# Sheet1.net
KiCad netlist of a schematic drawn in Altium Designer
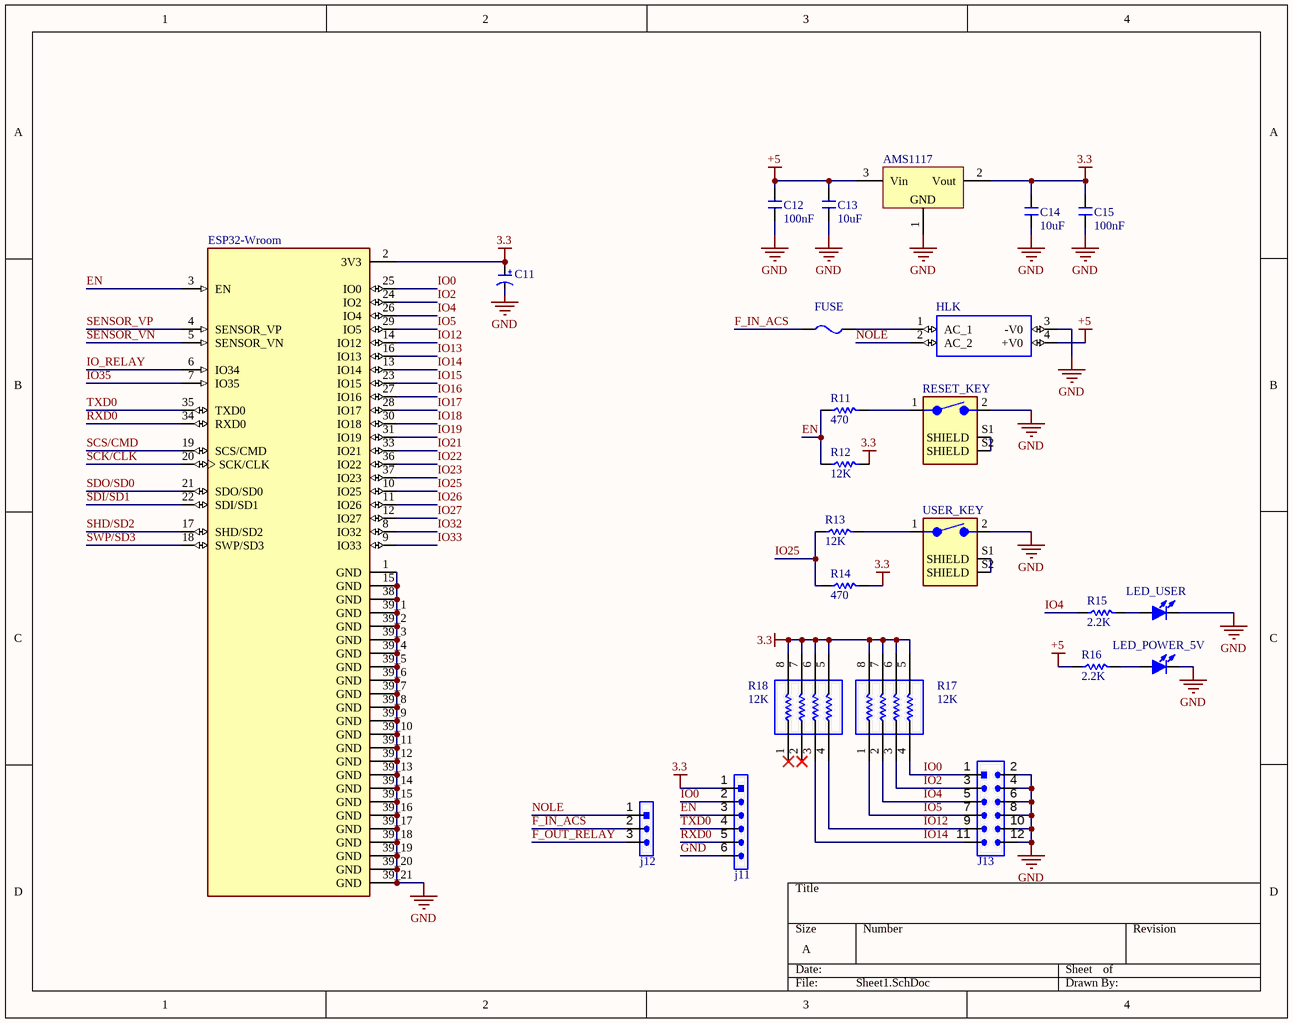
[diagram p0: Sheet1.SchDoc]

(export (version "E")
  (design (tool "Eeschema 10.0.6"))
  (components
    (comp (ref "AMS1117")
      (value "AMS1117-3V3")
      (footprint "SOT223_L")
      (description "Three-terminal regulator chip")
      (fields (field (name "版权归属") "源创客"))
      (libsource (lib "AltiumDesigner PCB Library") (part "AMS1117"))
    )
    (comp (ref "C11")
      (value "~")
      (footprint "CD A(3216)")
      (description "Solid Tantalum Chip Capacitor, Standard T491 Series - Industrial Grade")
      (fields (field (name "PUBLISHER") "Altium Limited"))
      (libsource (lib "AltiumDesigner PCB Library") (part "C-CD"))
    )
    (comp (ref "C12")
      (value "100nF")
      (footprint "C 0805")
      (description "Non-polar patch capacitor")
      (fields (field (name "版权归属") "源创客"))
      (libsource (lib "AltiumDesigner PCB Library") (part "C"))
    )
    (comp (ref "C13")
      (value "10uF")
      (footprint "C 0805")
      (description "Non-polar patch capacitor")
      (fields (field (name "版权归属") "源创客"))
      (libsource (lib "AltiumDesigner PCB Library") (part "C"))
    )
    (comp (ref "C14")
      (value "10uF")
      (footprint "C 0805")
      (description "Non-polar patch capacitor")
      (fields (field (name "版权归属") "源创客"))
      (libsource (lib "AltiumDesigner PCB Library") (part "C"))
    )
    (comp (ref "C15")
      (value "100nF")
      (footprint "C 0805")
      (description "Non-polar patch capacitor")
      (fields (field (name "版权归属") "源创客"))
      (libsource (lib "AltiumDesigner PCB Library") (part "C"))
    )
    (comp (ref "ESP32-Wroom")
      (value "ESP32-WROOM-32")
      (footprint "MODULE_ESP32-WROOM-32")
      (description "Bluetooth, WiFi Transceiver Module 2.4GHz ~ 2.5GHz Surface Mount")
      (fields (field (name "MF") "Espressif Systems") (field (name "DIGI-KEY_PART_NUMBER") "1904-1010-1-ND"))
      (libsource (lib "ESP32-WROOM-32") (part "ESP32-WROOM-32"))
    )
    (comp (ref "FUSE")
      (value "MSMD200-8V 2A")
      (footprint "FU 0805")
      (description "Chip fuse")
      (fields (field (name "版权归属") "源创客"))
      (libsource (lib "AltiumDesigner PCB Library") (part "FU"))
    )
    (comp (ref "HLK")
      (value "HLK-PM01")
      (footprint "HLKPM01")
      (fields (field (name "MF") "Hi-link") (field (name "MP") "hlk-pm01"))
      (libsource (lib "HLK-PM01") (part "HLK-PM01"))
    )
    (comp (ref "j11")
      (value "HDR-1X6")
      (footprint "HDR-1X6")
      (description "6P Connector")
      (fields (field (name "版权归属") "源创客"))
      (libsource (lib "AltiumDesigner PCB Library") (part "Header 6"))
    )
    (comp (ref "j12")
      (value "HDR-1X3")
      (footprint "HDR-1X3")
      (description "3P Connector")
      (fields (field (name "版权归属") "源创客"))
      (libsource (lib "AltiumDesigner PCB Library") (part "Header 3"))
    )
    (comp (ref "J13")
      (value "Header 6X2")
      (footprint "HDR-6X2")
      (description "6*2P Connector")
      (fields (field (name "版权归属") "源创客"))
      (libsource (lib "AltiumDesigner PCB Library") (part "Header  6X2"))
    )
    (comp (ref "LED_POWER_5V")
      (value "LED-SMD")
      (footprint "LED 0805R")
      (description "Patch LED")
      (fields (field (name "版权归属") "源创客"))
      (libsource (lib "AltiumDesigner PCB Library") (part "LED-SMD"))
    )
    (comp (ref "LED_USER")
      (value "LED-SMD")
      (footprint "LED 0805G")
      (description "Patch LED")
      (fields (field (name "版权归属") "源创客"))
      (libsource (lib "AltiumDesigner PCB Library") (part "LED-SMD"))
    )
    (comp (ref "R11")
      (value "470")
      (footprint "R 0805")
      (description "Chip resistor")
      (fields (field (name "版权归属") "源创客"))
      (libsource (lib "AltiumDesigner PCB Library") (part "R"))
    )
    (comp (ref "R12")
      (value "12K")
      (footprint "R 0805")
      (description "Chip resistor")
      (fields (field (name "版权归属") "源创客"))
      (libsource (lib "AltiumDesigner PCB Library") (part "R"))
    )
    (comp (ref "R13")
      (value "12K")
      (footprint "R 0805")
      (description "Chip resistor")
      (fields (field (name "版权归属") "源创客"))
      (libsource (lib "AltiumDesigner PCB Library") (part "R"))
    )
    (comp (ref "R14")
      (value "470")
      (footprint "R 0805")
      (description "Chip resistor")
      (fields (field (name "版权归属") "源创客"))
      (libsource (lib "AltiumDesigner PCB Library") (part "R"))
    )
    (comp (ref "R15")
      (value "2.2K")
      (footprint "R 0805")
      (description "Chip resistor")
      (fields (field (name "版权归属") "源创客"))
      (libsource (lib "AltiumDesigner PCB Library") (part "R"))
    )
    (comp (ref "R16")
      (value "2.2K")
      (footprint "R 0805")
      (description "Chip resistor")
      (fields (field (name "版权归属") "源创客"))
      (libsource (lib "AltiumDesigner PCB Library") (part "R"))
    )
    (comp (ref "R17")
      (value "12K")
      (footprint "RA0805 (4D02)-L")
      (description "4 way Chip Resistor Array")
      (libsource (lib "AltiumDesigner PCB Library") (part "R-ARR"))
    )
    (comp (ref "R18")
      (value "12K")
      (footprint "RA0805 (4D02)-L")
      (description "4 way Chip Resistor Array")
      (libsource (lib "AltiumDesigner PCB Library") (part "R-ARR"))
    )
    (comp (ref "RESET_KEY")
      (value "1-1825027-1")
      (footprint "SW_1-1825027-1")
      (description "Switch Push Button OFF _ON_ SPST Round Button 0.05A 24VDC Momentary Contact PC Pins Thru-Hole")
      (fields (field (name "MF") "TE Connectivity"))
      (libsource (lib "1-1825027-1") (part "1-1825027-1"))
    )
    (comp (ref "USER_KEY")
      (value "1-1825027-1")
      (footprint "SW_1-1825027-1")
      (description "Switch Push Button OFF _ON_ SPST Round Button 0.05A 24VDC Momentary Contact PC Pins Thru-Hole")
      (fields (field (name "MF") "TE Connectivity"))
      (libsource (lib "1-1825027-1") (part "1-1825027-1"))
    )
  )
  (nets
    (net (code "1") (name "+5") (class "Default")
      (node (ref "AMS1117") (pin "3") (pinfunction "Vin_3") (pintype "passive"))
      (node (ref "C12") (pin "2") (pinfunction "2_2") (pintype "passive"))
      (node (ref "C13") (pin "2") (pinfunction "2_2") (pintype "passive"))
      (node (ref "HLK") (pin "4") (pinfunction "+V0_4") (pintype "bidirectional"))
      (node (ref "R16") (pin "1") (pinfunction "1_1") (pintype "passive"))
    )
    (net (code "2") (name "/EN") (class "Default")
      (node (ref "ESP32-Wroom") (pin "3") (pinfunction "EN_3") (pintype "input"))
      (node (ref "R11") (pin "1") (pinfunction "1_1") (pintype "passive"))
      (node (ref "R12") (pin "1") (pinfunction "1_1") (pintype "passive"))
      (node (ref "j11") (pin "3") (pintype "passive"))
    )
    (net (code "3") (name "/F_IN_ACS") (class "Default")
      (node (ref "FUSE") (pin "1") (pinfunction "1_1") (pintype "passive"))
      (node (ref "j12") (pin "2") (pintype "passive"))
    )
    (net (code "4") (name "/F_OUT_RELAY") (class "Default") (node (ref "j12") (pin "3") (pintype "passive")))
    (net (code "5") (name "/IO0") (class "Default")
      (node (ref "ESP32-Wroom") (pin "25") (pinfunction "IO0_25") (pintype "bidirectional"))
      (node (ref "J13") (pin "1") (pintype "passive"))
      (node (ref "R17") (pin "4") (pinfunction "4_4") (pintype "passive"))
      (node (ref "j11") (pin "2") (pintype "passive"))
    )
    (net (code "6") (name "/IO2") (class "Default")
      (node (ref "ESP32-Wroom") (pin "24") (pinfunction "IO2_24") (pintype "bidirectional"))
      (node (ref "J13") (pin "3") (pintype "passive"))
      (node (ref "R17") (pin "3") (pinfunction "3_3") (pintype "passive"))
    )
    (net (code "7") (name "/IO4") (class "Default")
      (node (ref "ESP32-Wroom") (pin "26") (pinfunction "IO4_26") (pintype "bidirectional"))
      (node (ref "J13") (pin "5") (pintype "passive"))
      (node (ref "R15") (pin "1") (pinfunction "1_1") (pintype "passive"))
      (node (ref "R17") (pin "2") (pinfunction "2_2") (pintype "passive"))
    )
    (net (code "8") (name "/IO5") (class "Default")
      (node (ref "ESP32-Wroom") (pin "29") (pinfunction "IO5_29") (pintype "bidirectional"))
      (node (ref "J13") (pin "7") (pintype "passive"))
      (node (ref "R17") (pin "1") (pinfunction "1_1") (pintype "passive"))
    )
    (net (code "9") (name "/IO12") (class "Default")
      (node (ref "ESP32-Wroom") (pin "14") (pinfunction "IO12_14") (pintype "bidirectional"))
      (node (ref "J13") (pin "9") (pintype "passive"))
      (node (ref "R18") (pin "4") (pinfunction "4_4") (pintype "passive"))
    )
    (net (code "10") (name "/IO13") (class "Default")
      (node (ref "ESP32-Wroom") (pin "16") (pinfunction "IO13_16") (pintype "bidirectional"))
    )
    (net (code "11") (name "/IO14") (class "Default")
      (node (ref "ESP32-Wroom") (pin "13") (pinfunction "IO14_13") (pintype "bidirectional"))
      (node (ref "J13") (pin "11") (pintype "passive"))
      (node (ref "R18") (pin "3") (pinfunction "3_3") (pintype "passive"))
    )
    (net (code "12") (name "/IO15") (class "Default")
      (node (ref "ESP32-Wroom") (pin "23") (pinfunction "IO15_23") (pintype "bidirectional"))
    )
    (net (code "13") (name "/IO16") (class "Default")
      (node (ref "ESP32-Wroom") (pin "27") (pinfunction "IO16_27") (pintype "bidirectional"))
    )
    (net (code "14") (name "/IO17") (class "Default")
      (node (ref "ESP32-Wroom") (pin "28") (pinfunction "IO17_28") (pintype "bidirectional"))
    )
    (net (code "15") (name "/IO18") (class "Default")
      (node (ref "ESP32-Wroom") (pin "30") (pinfunction "IO18_30") (pintype "bidirectional"))
    )
    (net (code "16") (name "/IO19") (class "Default")
      (node (ref "ESP32-Wroom") (pin "31") (pinfunction "IO19_31") (pintype "bidirectional"))
    )
    (net (code "17") (name "/IO21") (class "Default")
      (node (ref "ESP32-Wroom") (pin "33") (pinfunction "IO21_33") (pintype "bidirectional"))
    )
    (net (code "18") (name "/IO22") (class "Default")
      (node (ref "ESP32-Wroom") (pin "36") (pinfunction "IO22_36") (pintype "bidirectional"))
    )
    (net (code "19") (name "/IO23") (class "Default")
      (node (ref "ESP32-Wroom") (pin "37") (pinfunction "IO23_37") (pintype "bidirectional"))
    )
    (net (code "20") (name "/IO25") (class "Default")
      (node (ref "ESP32-Wroom") (pin "10") (pinfunction "IO25_10") (pintype "bidirectional"))
      (node (ref "R13") (pin "1") (pinfunction "1_1") (pintype "passive"))
      (node (ref "R14") (pin "1") (pinfunction "1_1") (pintype "passive"))
    )
    (net (code "21") (name "/IO26") (class "Default")
      (node (ref "ESP32-Wroom") (pin "11") (pinfunction "IO26_11") (pintype "bidirectional"))
    )
    (net (code "22") (name "/IO27") (class "Default")
      (node (ref "ESP32-Wroom") (pin "12") (pinfunction "IO27_12") (pintype "bidirectional"))
    )
    (net (code "23") (name "/IO32") (class "Default")
      (node (ref "ESP32-Wroom") (pin "8") (pinfunction "IO32_8") (pintype "bidirectional"))
    )
    (net (code "24") (name "/IO33") (class "Default")
      (node (ref "ESP32-Wroom") (pin "9") (pinfunction "IO33_9") (pintype "bidirectional"))
    )
    (net (code "25") (name "/IO35") (class "Default")
      (node (ref "ESP32-Wroom") (pin "7") (pinfunction "IO35_7") (pintype "input"))
    )
    (net (code "26") (name "/IO_RELAY") (class "Default")
      (node (ref "ESP32-Wroom") (pin "6") (pinfunction "IO34_6") (pintype "input"))
    )
    (net (code "27") (name "/NOLE") (class "Default")
      (node (ref "HLK") (pin "2") (pinfunction "AC_2_2") (pintype "bidirectional"))
      (node (ref "j12") (pin "1") (pintype "passive"))
    )
    (net (code "28") (name "/RXD0") (class "Default")
      (node (ref "ESP32-Wroom") (pin "34") (pinfunction "RXD0_34") (pintype "bidirectional"))
      (node (ref "j11") (pin "5") (pintype "passive"))
    )
    (net (code "29") (name "/SCK{slash}CLK") (class "Default")
      (node (ref "ESP32-Wroom") (pin "20") (pinfunction "SCK/CLK_20") (pintype "bidirectional"))
    )
    (net (code "30") (name "/SCS{slash}CMD") (class "Default")
      (node (ref "ESP32-Wroom") (pin "19") (pinfunction "SCS/CMD_19") (pintype "bidirectional"))
    )
    (net (code "31") (name "/SDI{slash}SD1") (class "Default")
      (node (ref "ESP32-Wroom") (pin "22") (pinfunction "SDI/SD1_22") (pintype "bidirectional"))
    )
    (net (code "32") (name "/SDO{slash}SD0") (class "Default")
      (node (ref "ESP32-Wroom") (pin "21") (pinfunction "SDO/SD0_21") (pintype "bidirectional"))
    )
    (net (code "33") (name "/SENSOR_VN") (class "Default")
      (node (ref "ESP32-Wroom") (pin "5") (pinfunction "SENSOR_VN_5") (pintype "input"))
    )
    (net (code "34") (name "/SENSOR_VP") (class "Default")
      (node (ref "ESP32-Wroom") (pin "4") (pinfunction "SENSOR_VP_4") (pintype "input"))
    )
    (net (code "35") (name "/SHD{slash}SD2") (class "Default")
      (node (ref "ESP32-Wroom") (pin "17") (pinfunction "SHD/SD2_17") (pintype "bidirectional"))
    )
    (net (code "36") (name "/SWP{slash}SD3") (class "Default")
      (node (ref "ESP32-Wroom") (pin "18") (pinfunction "SWP/SD3_18") (pintype "bidirectional"))
    )
    (net (code "37") (name "/TXD0") (class "Default")
      (node (ref "ESP32-Wroom") (pin "35") (pinfunction "TXD0_35") (pintype "bidirectional"))
      (node (ref "j11") (pin "4") (pintype "passive"))
    )
    (net (code "38") (name "3.3") (class "Default")
      (node (ref "AMS1117") (pin "2") (pinfunction "Vout_2") (pintype "passive"))
      (node (ref "C11") (pin "1") (pinfunction "A_1") (pintype "passive"))
      (node (ref "C14") (pin "2") (pinfunction "2_2") (pintype "passive"))
      (node (ref "C15") (pin "2") (pinfunction "2_2") (pintype "passive"))
      (node (ref "ESP32-Wroom") (pin "2") (pinfunction "3V3_2") (pintype "power_in"))
      (node (ref "R12") (pin "2") (pinfunction "2_2") (pintype "passive"))
      (node (ref "R14") (pin "2") (pinfunction "2_2") (pintype "passive"))
      (node (ref "R17") (pin "5") (pinfunction "5_5") (pintype "passive"))
      (node (ref "R17") (pin "6") (pinfunction "6_6") (pintype "passive"))
      (node (ref "R17") (pin "7") (pinfunction "7_7") (pintype "passive"))
      (node (ref "R17") (pin "8") (pinfunction "8_8") (pintype "passive"))
      (node (ref "R18") (pin "5") (pinfunction "5_5") (pintype "passive"))
      (node (ref "R18") (pin "6") (pinfunction "6_6") (pintype "passive"))
      (node (ref "R18") (pin "7") (pinfunction "7_7") (pintype "passive"))
      (node (ref "R18") (pin "8") (pinfunction "8_8") (pintype "passive"))
      (node (ref "j11") (pin "1") (pintype "passive"))
    )
    (net (code "39") (name "GND") (class "Default")
      (node (ref "AMS1117") (pin "1") (pinfunction "GND_1") (pintype "passive"))
      (node (ref "C11") (pin "2") (pinfunction "K_2") (pintype "passive"))
      (node (ref "C12") (pin "1") (pinfunction "1_1") (pintype "passive"))
      (node (ref "C13") (pin "1") (pinfunction "1_1") (pintype "passive"))
      (node (ref "C14") (pin "1") (pinfunction "1_1") (pintype "passive"))
      (node (ref "C15") (pin "1") (pinfunction "1_1") (pintype "passive"))
      (node (ref "ESP32-Wroom") (pin "1") (pinfunction "GND_1") (pintype "power_in"))
      (node (ref "ESP32-Wroom") (pin "15") (pinfunction "GND_15") (pintype "power_in"))
      (node (ref "ESP32-Wroom") (pin "38") (pinfunction "GND_38") (pintype "power_in"))
      (node (ref "ESP32-Wroom") (pin "39_1") (pinfunction "GND_39_1") (pintype "power_in"))
      (node (ref "ESP32-Wroom") (pin "39_10") (pinfunction "GND_39_10") (pintype "power_in"))
      (node (ref "ESP32-Wroom") (pin "39_11") (pinfunction "GND_39_11") (pintype "power_in"))
      (node (ref "ESP32-Wroom") (pin "39_12") (pinfunction "GND_39_12") (pintype "power_in"))
      (node (ref "ESP32-Wroom") (pin "39_13") (pinfunction "GND_39_13") (pintype "power_in"))
      (node (ref "ESP32-Wroom") (pin "39_14") (pinfunction "GND_39_14") (pintype "power_in"))
      (node (ref "ESP32-Wroom") (pin "39_15") (pinfunction "GND_39_15") (pintype "power_in"))
      (node (ref "ESP32-Wroom") (pin "39_16") (pinfunction "GND_39_16") (pintype "power_in"))
      (node (ref "ESP32-Wroom") (pin "39_17") (pinfunction "GND_39_17") (pintype "power_in"))
      (node (ref "ESP32-Wroom") (pin "39_18") (pinfunction "GND_39_18") (pintype "power_in"))
      (node (ref "ESP32-Wroom") (pin "39_19") (pinfunction "GND_39_19") (pintype "power_in"))
      (node (ref "ESP32-Wroom") (pin "39_2") (pinfunction "GND_39_2") (pintype "power_in"))
      (node (ref "ESP32-Wroom") (pin "39_20") (pinfunction "GND_39_20") (pintype "power_in"))
      (node (ref "ESP32-Wroom") (pin "39_21") (pinfunction "GND_39_21") (pintype "power_in"))
      (node (ref "ESP32-Wroom") (pin "39_3") (pinfunction "GND_39_3") (pintype "power_in"))
      (node (ref "ESP32-Wroom") (pin "39_4") (pinfunction "GND_39_4") (pintype "power_in"))
      (node (ref "ESP32-Wroom") (pin "39_5") (pinfunction "GND_39_5") (pintype "power_in"))
      (node (ref "ESP32-Wroom") (pin "39_6") (pinfunction "GND_39_6") (pintype "power_in"))
      (node (ref "ESP32-Wroom") (pin "39_7") (pinfunction "GND_39_7") (pintype "power_in"))
      (node (ref "ESP32-Wroom") (pin "39_8") (pinfunction "GND_39_8") (pintype "power_in"))
      (node (ref "ESP32-Wroom") (pin "39_9") (pinfunction "GND_39_9") (pintype "power_in"))
      (node (ref "HLK") (pin "3") (pinfunction "-V0_3") (pintype "bidirectional"))
      (node (ref "J13") (pin "10") (pintype "passive"))
      (node (ref "J13") (pin "12") (pintype "passive"))
      (node (ref "J13") (pin "2") (pintype "passive"))
      (node (ref "J13") (pin "4") (pintype "passive"))
      (node (ref "J13") (pin "6") (pintype "passive"))
      (node (ref "J13") (pin "8") (pintype "passive"))
      (node (ref "LED_POWER_5V") (pin "2") (pinfunction "K_2") (pintype "passive"))
      (node (ref "LED_USER") (pin "2") (pinfunction "K_2") (pintype "passive"))
      (node (ref "RESET_KEY") (pin "2") (pinfunction "2_2") (pintype "passive"))
      (node (ref "USER_KEY") (pin "2") (pinfunction "2_2") (pintype "passive"))
      (node (ref "j11") (pin "6") (pintype "passive"))
    )
    (net (code "40") (name "Net-(HLK-AC_1)") (class "Default")
      (node (ref "FUSE") (pin "2") (pinfunction "2_2") (pintype "passive"))
      (node (ref "HLK") (pin "1") (pinfunction "AC_1_1") (pintype "bidirectional"))
    )
    (net (code "41") (name "Net-(LED_POWER_5V-A)") (class "Default")
      (node (ref "LED_POWER_5V") (pin "1") (pinfunction "A_1") (pintype "passive"))
      (node (ref "R16") (pin "2") (pinfunction "2_2") (pintype "passive"))
    )
    (net (code "42") (name "Net-(LED_USER-A)") (class "Default")
      (node (ref "LED_USER") (pin "1") (pinfunction "A_1") (pintype "passive"))
      (node (ref "R15") (pin "2") (pinfunction "2_2") (pintype "passive"))
    )
    (net (code "43") (name "Net-(R11-Pad2)") (class "Default")
      (node (ref "R11") (pin "2") (pinfunction "2_2") (pintype "passive"))
      (node (ref "RESET_KEY") (pin "1") (pinfunction "1_1") (pintype "passive"))
    )
    (net (code "44") (name "Net-(R13-Pad2)") (class "Default")
      (node (ref "R13") (pin "2") (pinfunction "2_2") (pintype "passive"))
      (node (ref "USER_KEY") (pin "1") (pinfunction "1_1") (pintype "passive"))
    )
    (net (code "45") (name "Net-(RESET_KEY-SHIELD-PadS1)") (class "Default")
      (node (ref "RESET_KEY") (pin "S1") (pinfunction "SHIELD_S1") (pintype "power_in"))
      (node (ref "RESET_KEY") (pin "S2") (pinfunction "SHIELD_S2") (pintype "power_in"))
    )
    (net (code "46") (name "Net-(USER_KEY-SHIELD-PadS1)") (class "Default")
      (node (ref "USER_KEY") (pin "S1") (pinfunction "SHIELD_S1") (pintype "power_in"))
      (node (ref "USER_KEY") (pin "S2") (pinfunction "SHIELD_S2") (pintype "power_in"))
    )
    (net (code "47") (name "unconnected-(R18-Pad1)") (class "Default")
      (node (ref "R18") (pin "1") (pinfunction "1_1") (pintype "passive+no_connect"))
    )
    (net (code "48") (name "unconnected-(R18-Pad2)") (class "Default")
      (node (ref "R18") (pin "2") (pinfunction "2_2") (pintype "passive+no_connect"))
    )
  )
)
